# S5D3_MCU_only_edge_Power_SPI.net
KiCad netlist of a schematic drawn in EAGLE
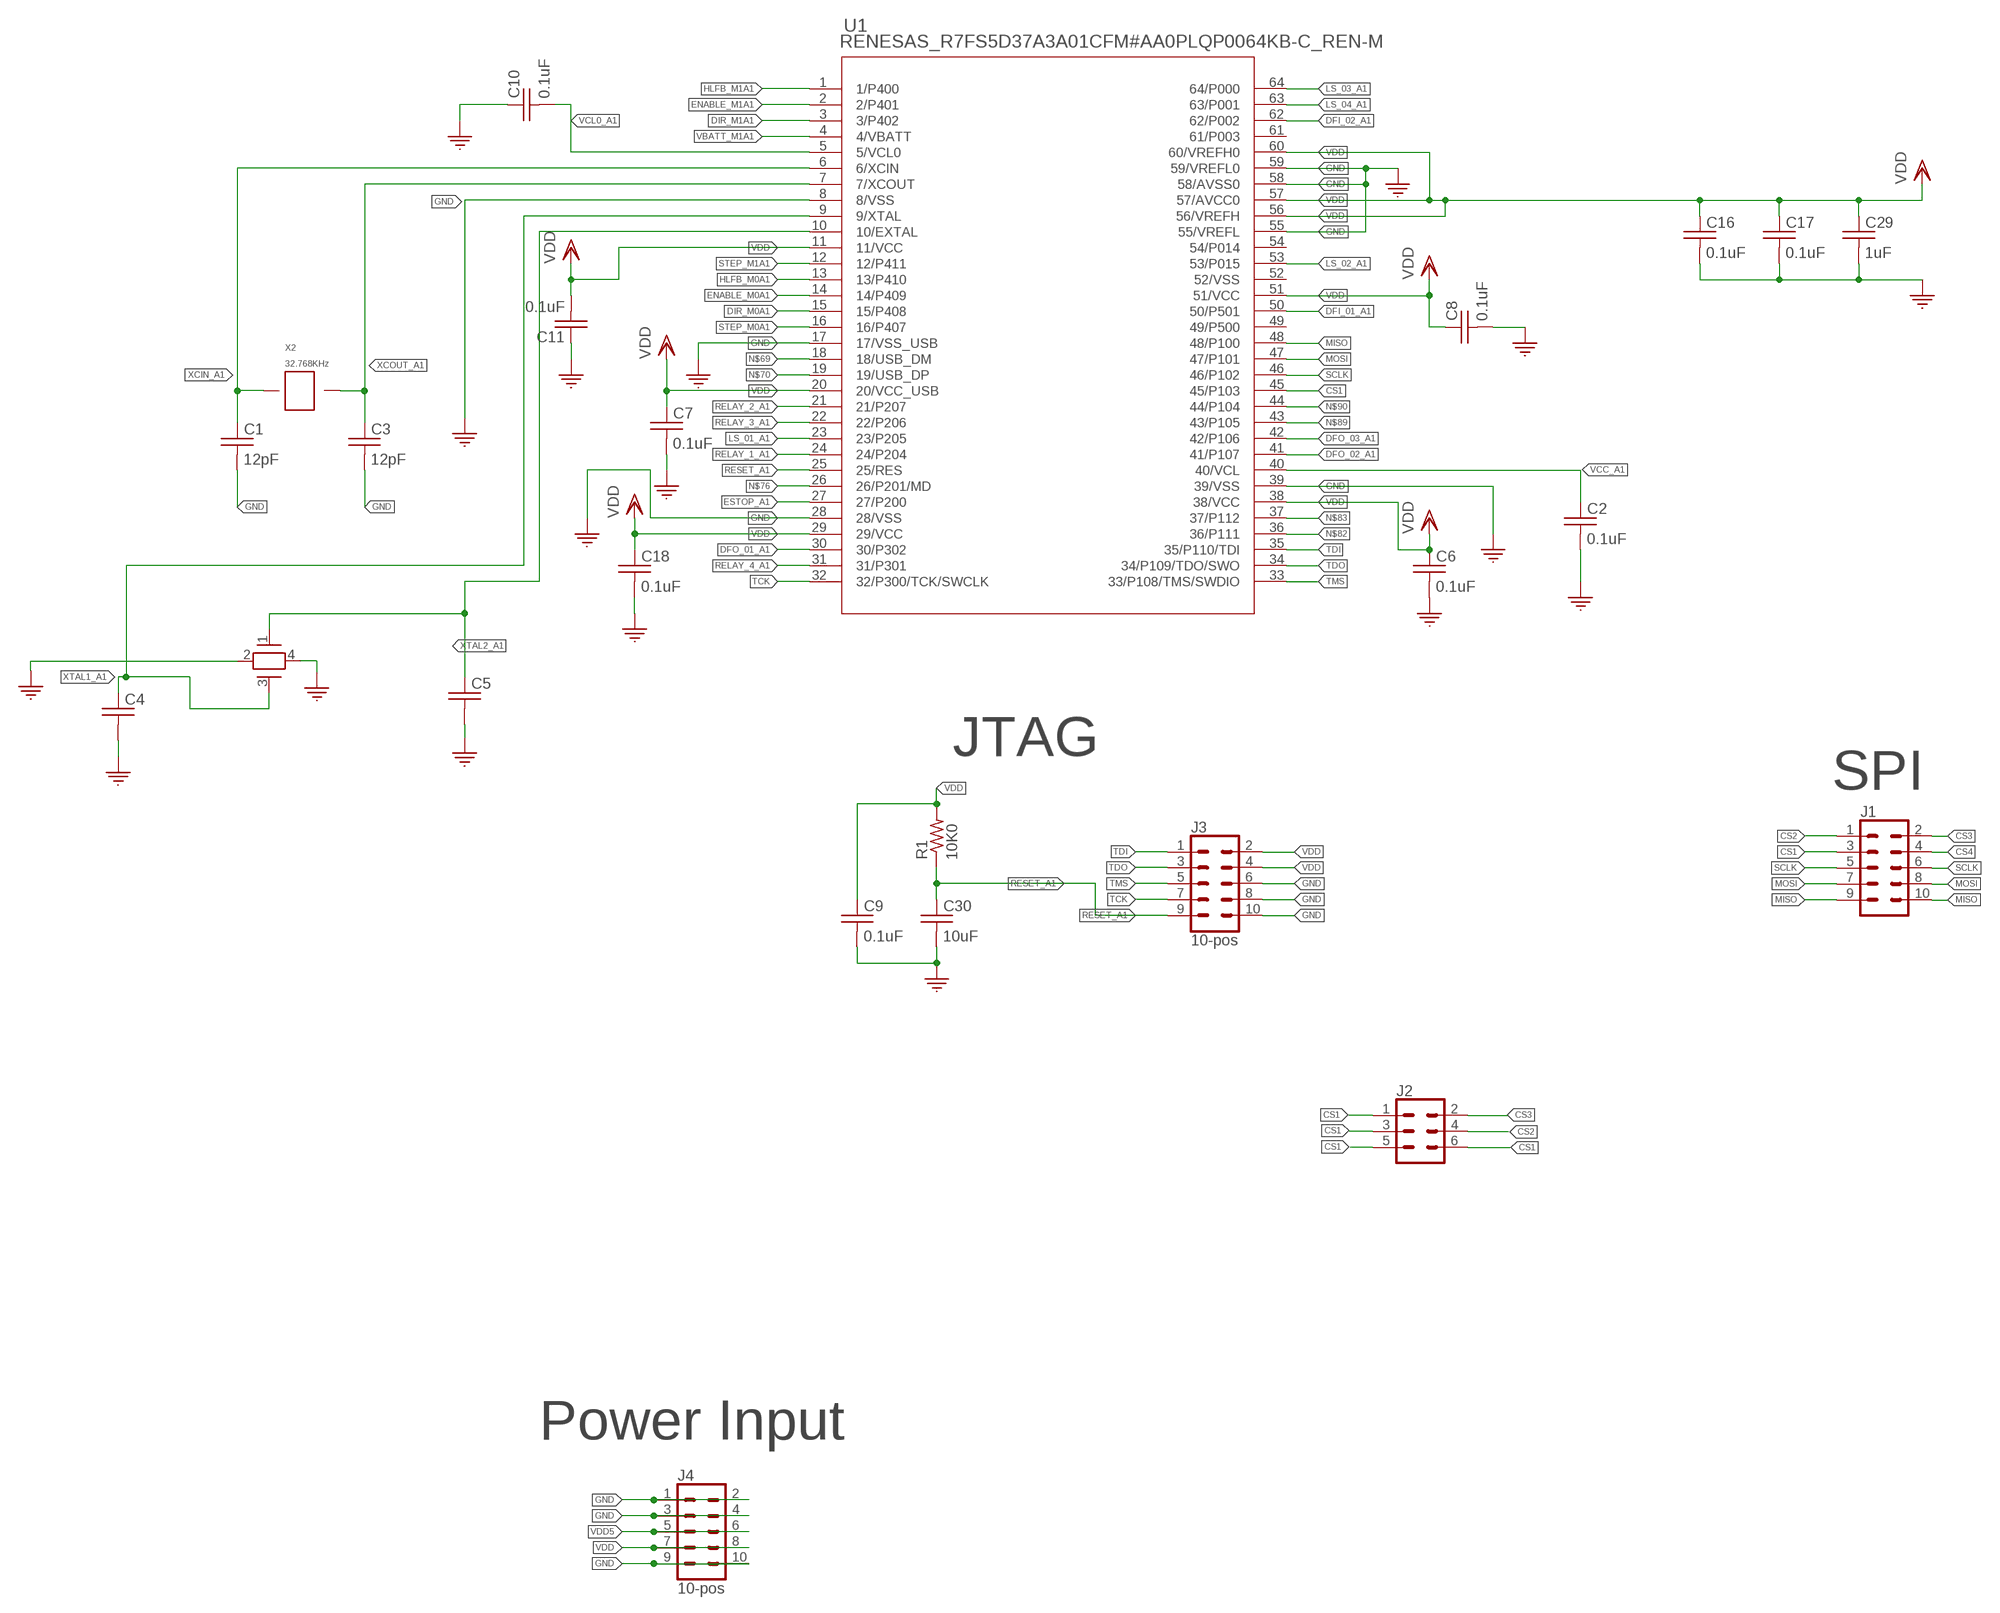
[diagram p0: schematic, sheet 1]

(export (version "E")
  (design (tool "Eeschema 10.0.6"))
  (components
    (comp (ref "C1")
      (value "12pF")
      (footprint "eagle-import:0402")
      (fields (field (name "PARTNO") "CL05C120JB5NNNC"))
      (libsource (lib "eagle-import") (part "C_0402_12PF"))
    )
    (comp (ref "C2")
      (value "0.1uF")
      (footprint "eagle-import:0402")
      (fields (field (name "PARTNO") "CL05F104ZO5NNNC"))
      (libsource (lib "eagle-import") (part "C_0402_0.1UF"))
    )
    (comp (ref "C3")
      (value "12pF")
      (footprint "eagle-import:0402")
      (fields (field (name "PARTNO") "CL05C120JB5NNNC"))
      (libsource (lib "eagle-import") (part "C_0402_12PF"))
    )
    (comp (ref "C4")
      (value "10pF")
      (footprint "eagle-import:0402")
      (fields (field (name "PARTNO") "CC0402JRNPO9BN100"))
      (libsource (lib "eagle-import") (part "C_0402_10PF"))
    )
    (comp (ref "C5")
      (value "10pF")
      (footprint "eagle-import:0402")
      (fields (field (name "PARTNO") "CC0402JRNPO9BN100"))
      (libsource (lib "eagle-import") (part "C_0402_10PF"))
    )
    (comp (ref "C6")
      (value "0.1uF")
      (footprint "eagle-import:0402")
      (fields (field (name "PARTNO") "CL05F104ZO5NNNC"))
      (libsource (lib "eagle-import") (part "C_0402_0.1UF"))
    )
    (comp (ref "C7")
      (value "0.1uF")
      (footprint "eagle-import:0402")
      (fields (field (name "PARTNO") "CL05F104ZO5NNNC"))
      (libsource (lib "eagle-import") (part "C_0402_0.1UF"))
    )
    (comp (ref "C8")
      (value "0.1uF")
      (footprint "eagle-import:0402")
      (fields (field (name "PARTNO") "CL05F104ZO5NNNC"))
      (libsource (lib "eagle-import") (part "C_0402_0.1UF"))
    )
    (comp (ref "C9")
      (value "0.1uF")
      (footprint "eagle-import:0402")
      (fields (field (name "PARTNO") "CL05F104ZO5NNNC"))
      (libsource (lib "eagle-import") (part "C_0402_0.1UF"))
    )
    (comp (ref "C10")
      (value "0.1uF")
      (footprint "eagle-import:0402")
      (fields (field (name "PARTNO") "CL05F104ZO5NNNC"))
      (libsource (lib "eagle-import") (part "C_0402_0.1UF"))
    )
    (comp (ref "C11")
      (value "0.1uF")
      (footprint "eagle-import:0402")
      (fields (field (name "PARTNO") "CL05F104ZO5NNNC"))
      (libsource (lib "eagle-import") (part "C_0402_0.1UF"))
    )
    (comp (ref "C16")
      (value "0.1uF")
      (footprint "eagle-import:0402")
      (fields (field (name "PARTNO") "CL05F104ZO5NNNC"))
      (libsource (lib "eagle-import") (part "C_0402_0.1UF"))
    )
    (comp (ref "C17")
      (value "0.1uF")
      (footprint "eagle-import:0402")
      (fields (field (name "PARTNO") "CL05F104ZO5NNNC"))
      (libsource (lib "eagle-import") (part "C_0402_0.1UF"))
    )
    (comp (ref "C18")
      (value "0.1uF")
      (footprint "eagle-import:0402")
      (fields (field (name "PARTNO") "CL05F104ZO5NNNC"))
      (libsource (lib "eagle-import") (part "C_0402_0.1UF"))
    )
    (comp (ref "C29")
      (value "1uF")
      (footprint "eagle-import:0402")
      (fields (field (name "PARTNO") "CL05A105KO5NNNC"))
      (libsource (lib "eagle-import") (part "C_0402_1UF"))
    )
    (comp (ref "C30")
      (value "10uF")
      (footprint "eagle-import:0402")
      (fields (field (name "PARTNO") "CL05A106MP8NUB8"))
      (libsource (lib "eagle-import") (part "C_0402_10UF"))
    )
    (comp (ref "J1")
      (value "CONN_05X2PTH")
      (footprint "eagle-import:2X5")
      (libsource (lib "eagle-import") (part "CONN_05X2PTH"))
    )
    (comp (ref "J2")
      (value "CONN_03X2")
      (footprint "eagle-import:2X3")
      (libsource (lib "eagle-import") (part "CONN_03X2"))
    )
    (comp (ref "J3")
      (value "10-pos")
      (footprint "eagle-import:2X5")
      (fields (field (name "PARTNO") "PH2RA-10-UA"))
      (libsource (lib "eagle-import") (part "CONN_05X2_RAPTH"))
    )
    (comp (ref "J4")
      (value "10-pos")
      (footprint "eagle-import:2X5")
      (fields (field (name "PARTNO") "PH2RA-10-UA"))
      (libsource (lib "eagle-import") (part "CONN_05X2_RAPTH"))
    )
    (comp (ref "R1")
      (value "10K0")
      (footprint "eagle-import:0402")
      (fields (field (name "PARTNO") "RMCF0402JT10K0"))
      (libsource (lib "eagle-import") (part "R_0402_10K0"))
    )
    (comp (ref "U1")
      (value "RENESAS_R7FS5D37A3A01CFM#AA0PLQP0064KB-C_REN-M")
      (footprint "eagle-import:PLQP0064KB-C_REN-M")
      (fields
        (field (name "PARTNO") "R7FS3A37A3A01CFM#AA0")
        (field (name "COPYRIGHT") "Copyright (C) 2023 Ultra Librarian. All rights reserved.")
      )
      (libsource (lib "eagle-import") (part "RENESAS_R7FS5D37A3A01CFM#AA0PLQP0064KB-C_REN-M"))
    )
    (comp (ref "X2")
      (value "32.768KHz")
      (footprint "eagle-import:SMD_X_2_PADS")
      (fields (field (name "PARTNO") "ABS07-32.768KHZ-T"))
      (libsource (lib "eagle-import") (part "XTAL_32.768KHZ"))
    )
    (comp (ref "Y1")
      (value "XTAL_12MHZ_ABM8G-12.000MHZ-B4Y-T")
      (footprint "eagle-import:CRYSTAL_ABM8G_ABR")
      (fields
        (field (name "PARTNO") "ABM8G-12.000MHZ-B4Y-T")
        (field (name "COPYRIGHT") "Copyright (C) 2023 Ultra Librarian. All rights reserved.")
      )
      (libsource (lib "eagle-import") (part "XTAL_12MHZ_ABM8G-12.000MHZ-B4Y-T"))
    )
  )
  (nets
    (net (code "1") (name "CS1") (class "Default")
      (node (ref "J1") (pin "3") (pinfunction "3_3") (pintype "passive"))
      (node (ref "J2") (pin "1") (pinfunction "1_1") (pintype "passive"))
      (node (ref "J2") (pin "3") (pinfunction "3_3") (pintype "passive"))
      (node (ref "J2") (pin "5") (pinfunction "5_5") (pintype "passive"))
      (node (ref "J2") (pin "6") (pinfunction "6_6") (pintype "passive"))
      (node (ref "U1") (pin "45") (pinfunction "45/P103_45") (pintype "bidirectional"))
    )
    (net (code "2") (name "CS2") (class "Default")
      (node (ref "J1") (pin "1") (pinfunction "1_1") (pintype "passive"))
      (node (ref "J2") (pin "4") (pinfunction "4_4") (pintype "passive"))
    )
    (net (code "3") (name "CS3") (class "Default")
      (node (ref "J1") (pin "2") (pinfunction "2_2") (pintype "passive"))
      (node (ref "J2") (pin "2") (pinfunction "2_2") (pintype "passive"))
    )
    (net (code "4") (name "CS4") (class "Default")
      (node (ref "J1") (pin "4") (pinfunction "4_4") (pintype "passive"))
    )
    (net (code "5") (name "DFI_01_A1") (class "Default")
      (node (ref "U1") (pin "50") (pinfunction "50/P501_50") (pintype "bidirectional"))
    )
    (net (code "6") (name "DFI_02_A1") (class "Default")
      (node (ref "U1") (pin "62") (pinfunction "62/P002_62") (pintype "bidirectional"))
    )
    (net (code "7") (name "DFO_01_A1") (class "Default")
      (node (ref "U1") (pin "30") (pinfunction "30/P302_30") (pintype "bidirectional"))
    )
    (net (code "8") (name "DFO_02_A1") (class "Default")
      (node (ref "U1") (pin "41") (pinfunction "41/P107_41") (pintype "bidirectional"))
    )
    (net (code "9") (name "DFO_03_A1") (class "Default")
      (node (ref "U1") (pin "42") (pinfunction "42/P106_42") (pintype "bidirectional"))
    )
    (net (code "10") (name "DIR_M0A1") (class "Default")
      (node (ref "U1") (pin "15") (pinfunction "15/P408_15") (pintype "bidirectional"))
    )
    (net (code "11") (name "DIR_M1A1") (class "Default")
      (node (ref "U1") (pin "3") (pinfunction "3/P402_3") (pintype "bidirectional"))
    )
    (net (code "12") (name "ENABLE_M0A1") (class "Default")
      (node (ref "U1") (pin "14") (pinfunction "14/P409_14") (pintype "bidirectional"))
    )
    (net (code "13") (name "ENABLE_M1A1") (class "Default")
      (node (ref "U1") (pin "2") (pinfunction "2/P401_2") (pintype "bidirectional"))
    )
    (net (code "14") (name "ESTOP_A1") (class "Default")
      (node (ref "U1") (pin "27") (pinfunction "27/P200_27") (pintype "bidirectional"))
    )
    (net (code "15") (name "GND") (class "Default")
      (node (ref "C1") (pin "P$2") (pinfunction "2_P$2") (pintype "passive"))
      (node (ref "C10") (pin "P$1") (pinfunction "1_P$1") (pintype "passive"))
      (node (ref "C11") (pin "P$1") (pinfunction "1_P$1") (pintype "passive"))
      (node (ref "C16") (pin "P$2") (pinfunction "2_P$2") (pintype "passive"))
      (node (ref "C17") (pin "P$2") (pinfunction "2_P$2") (pintype "passive"))
      (node (ref "C18") (pin "P$2") (pinfunction "2_P$2") (pintype "passive"))
      (node (ref "C2") (pin "P$2") (pinfunction "2_P$2") (pintype "passive"))
      (node (ref "C29") (pin "P$2") (pinfunction "2_P$2") (pintype "passive"))
      (node (ref "C3") (pin "P$2") (pinfunction "2_P$2") (pintype "passive"))
      (node (ref "C30") (pin "P$2") (pinfunction "2_P$2") (pintype "passive"))
      (node (ref "C4") (pin "P$2") (pinfunction "2_P$2") (pintype "passive"))
      (node (ref "C5") (pin "P$2") (pinfunction "2_P$2") (pintype "passive"))
      (node (ref "C6") (pin "P$2") (pinfunction "2_P$2") (pintype "passive"))
      (node (ref "C7") (pin "P$2") (pinfunction "2_P$2") (pintype "passive"))
      (node (ref "C8") (pin "P$2") (pinfunction "2_P$2") (pintype "passive"))
      (node (ref "C9") (pin "P$2") (pinfunction "2_P$2") (pintype "passive"))
      (node (ref "J3") (pin "10") (pinfunction "10_10") (pintype "passive"))
      (node (ref "J3") (pin "6") (pinfunction "6_6") (pintype "passive"))
      (node (ref "J3") (pin "8") (pinfunction "8_8") (pintype "passive"))
      (node (ref "J4") (pin "1") (pinfunction "1_1") (pintype "passive"))
      (node (ref "J4") (pin "10") (pinfunction "10_10") (pintype "passive"))
      (node (ref "J4") (pin "2") (pinfunction "2_2") (pintype "passive"))
      (node (ref "J4") (pin "3") (pinfunction "3_3") (pintype "passive"))
      (node (ref "J4") (pin "4") (pinfunction "4_4") (pintype "passive"))
      (node (ref "J4") (pin "9") (pinfunction "9_9") (pintype "passive"))
      (node (ref "U1") (pin "17") (pinfunction "17/VSS_USB_17") (pintype "power_in"))
      (node (ref "U1") (pin "28") (pinfunction "28/VSS_28") (pintype "bidirectional"))
      (node (ref "U1") (pin "39") (pinfunction "39/VSS_39") (pintype "power_in"))
      (node (ref "U1") (pin "55") (pinfunction "55/VREFL_55") (pintype "bidirectional"))
      (node (ref "U1") (pin "58") (pinfunction "58/AVSS0_58") (pintype "bidirectional"))
      (node (ref "U1") (pin "59") (pinfunction "59/VREFL0_59") (pintype "bidirectional"))
      (node (ref "U1") (pin "8") (pinfunction "8/VSS_8") (pintype "power_in"))
      (node (ref "Y1") (pin "2") (pinfunction "2_2") (pintype "passive"))
      (node (ref "Y1") (pin "4") (pinfunction "4_4") (pintype "passive"))
    )
    (net (code "16") (name "HLFB_M0A1") (class "Default")
      (node (ref "U1") (pin "13") (pinfunction "13/P410_13") (pintype "bidirectional"))
    )
    (net (code "17") (name "HLFB_M1A1") (class "Default")
      (node (ref "U1") (pin "1") (pinfunction "1/P400_1") (pintype "bidirectional"))
    )
    (net (code "18") (name "LS_01_A1") (class "Default")
      (node (ref "U1") (pin "23") (pinfunction "23/P205_23") (pintype "bidirectional"))
    )
    (net (code "19") (name "LS_02_A1") (class "Default")
      (node (ref "U1") (pin "53") (pinfunction "53/P015_53") (pintype "bidirectional"))
    )
    (net (code "20") (name "LS_03_A1") (class "Default")
      (node (ref "U1") (pin "64") (pinfunction "64/P000_64") (pintype "bidirectional"))
    )
    (net (code "21") (name "LS_04_A1") (class "Default")
      (node (ref "U1") (pin "63") (pinfunction "63/P001_63") (pintype "bidirectional"))
    )
    (net (code "22") (name "MISO") (class "Default")
      (node (ref "J1") (pin "10") (pinfunction "10_10") (pintype "passive"))
      (node (ref "J1") (pin "9") (pinfunction "9_9") (pintype "passive"))
      (node (ref "U1") (pin "48") (pinfunction "48/P100_48") (pintype "bidirectional"))
    )
    (net (code "23") (name "MOSI") (class "Default")
      (node (ref "J1") (pin "7") (pinfunction "7_7") (pintype "passive"))
      (node (ref "J1") (pin "8") (pinfunction "8_8") (pintype "passive"))
      (node (ref "U1") (pin "47") (pinfunction "47/P101_47") (pintype "bidirectional"))
    )
    (net (code "24") (name "N$69") (class "Default")
      (node (ref "U1") (pin "18") (pinfunction "18/USB_DM_18") (pintype "bidirectional"))
    )
    (net (code "25") (name "N$70") (class "Default")
      (node (ref "U1") (pin "19") (pinfunction "19/USB_DP_19") (pintype "bidirectional"))
    )
    (net (code "26") (name "N$76") (class "Default")
      (node (ref "U1") (pin "26") (pinfunction "26/P201/MD_26") (pintype "bidirectional"))
    )
    (net (code "27") (name "N$82") (class "Default")
      (node (ref "U1") (pin "36") (pinfunction "36/P111_36") (pintype "bidirectional"))
    )
    (net (code "28") (name "N$83") (class "Default")
      (node (ref "U1") (pin "37") (pinfunction "37/P112_37") (pintype "bidirectional"))
    )
    (net (code "29") (name "N$89") (class "Default")
      (node (ref "U1") (pin "43") (pinfunction "43/P105_43") (pintype "bidirectional"))
    )
    (net (code "30") (name "N$90") (class "Default")
      (node (ref "U1") (pin "44") (pinfunction "44/P104_44") (pintype "bidirectional"))
    )
    (net (code "31") (name "RELAY_1_A1") (class "Default")
      (node (ref "U1") (pin "24") (pinfunction "24/P204_24") (pintype "bidirectional"))
    )
    (net (code "32") (name "RELAY_2_A1") (class "Default")
      (node (ref "U1") (pin "21") (pinfunction "21/P207_21") (pintype "power_in"))
    )
    (net (code "33") (name "RELAY_3_A1") (class "Default")
      (node (ref "U1") (pin "22") (pinfunction "22/P206_22") (pintype "bidirectional"))
    )
    (net (code "34") (name "RELAY_4_A1") (class "Default")
      (node (ref "U1") (pin "31") (pinfunction "31/P301_31") (pintype "bidirectional"))
    )
    (net (code "35") (name "RESET_A1") (class "Default")
      (node (ref "C30") (pin "P$1") (pinfunction "1_P$1") (pintype "passive"))
      (node (ref "J3") (pin "9") (pinfunction "9_9") (pintype "passive"))
      (node (ref "R1") (pin "P$1") (pinfunction "1_P$1") (pintype "passive"))
      (node (ref "U1") (pin "25") (pinfunction "25/RES_25") (pintype "input"))
    )
    (net (code "36") (name "SCLK") (class "Default")
      (node (ref "J1") (pin "5") (pinfunction "5_5") (pintype "passive"))
      (node (ref "J1") (pin "6") (pinfunction "6_6") (pintype "passive"))
      (node (ref "U1") (pin "46") (pinfunction "46/P102_46") (pintype "bidirectional"))
    )
    (net (code "37") (name "STEP_M0A1") (class "Default")
      (node (ref "U1") (pin "16") (pinfunction "16/P407_16") (pintype "bidirectional"))
    )
    (net (code "38") (name "STEP_M1A1") (class "Default")
      (node (ref "U1") (pin "12") (pinfunction "12/P411_12") (pintype "bidirectional"))
    )
    (net (code "39") (name "TCK") (class "Default")
      (node (ref "J3") (pin "7") (pinfunction "7_7") (pintype "passive"))
      (node (ref "U1") (pin "32") (pinfunction "32/P300/TCK/SWCLK_32") (pintype "bidirectional"))
    )
    (net (code "40") (name "TDI") (class "Default")
      (node (ref "J3") (pin "1") (pinfunction "1_1") (pintype "passive"))
      (node (ref "U1") (pin "35") (pinfunction "35/P110/TDI_35") (pintype "bidirectional"))
    )
    (net (code "41") (name "TDO") (class "Default")
      (node (ref "J3") (pin "3") (pinfunction "3_3") (pintype "passive"))
      (node (ref "U1") (pin "34") (pinfunction "34/P109/TDO/SWO_34") (pintype "bidirectional"))
    )
    (net (code "42") (name "TMS") (class "Default")
      (node (ref "J3") (pin "5") (pinfunction "5_5") (pintype "passive"))
      (node (ref "U1") (pin "33") (pinfunction "33/P108/TMS/SWDIO_33") (pintype "bidirectional"))
    )
    (net (code "43") (name "VBATT_M1A1") (class "Default")
      (node (ref "U1") (pin "4") (pinfunction "4/VBATT_4") (pintype "power_in"))
    )
    (net (code "44") (name "VCC_A1") (class "Default")
      (node (ref "C2") (pin "P$1") (pinfunction "1_P$1") (pintype "passive"))
      (node (ref "U1") (pin "40") (pinfunction "40/VCL_40") (pintype "power_in"))
    )
    (net (code "45") (name "VCL0_A1") (class "Default")
      (node (ref "C10") (pin "P$2") (pinfunction "2_P$2") (pintype "passive"))
      (node (ref "U1") (pin "5") (pinfunction "5/VCL0_5") (pintype "power_in"))
    )
    (net (code "46") (name "VDD") (class "Default")
      (node (ref "C11") (pin "P$2") (pinfunction "2_P$2") (pintype "passive"))
      (node (ref "C16") (pin "P$1") (pinfunction "1_P$1") (pintype "passive"))
      (node (ref "C17") (pin "P$1") (pinfunction "1_P$1") (pintype "passive"))
      (node (ref "C18") (pin "P$1") (pinfunction "1_P$1") (pintype "passive"))
      (node (ref "C29") (pin "P$1") (pinfunction "1_P$1") (pintype "passive"))
      (node (ref "C6") (pin "P$1") (pinfunction "1_P$1") (pintype "passive"))
      (node (ref "C7") (pin "P$1") (pinfunction "1_P$1") (pintype "passive"))
      (node (ref "C8") (pin "P$1") (pinfunction "1_P$1") (pintype "passive"))
      (node (ref "C9") (pin "P$1") (pinfunction "1_P$1") (pintype "passive"))
      (node (ref "J3") (pin "2") (pinfunction "2_2") (pintype "passive"))
      (node (ref "J3") (pin "4") (pinfunction "4_4") (pintype "passive"))
      (node (ref "J4") (pin "7") (pinfunction "7_7") (pintype "passive"))
      (node (ref "J4") (pin "8") (pinfunction "8_8") (pintype "passive"))
      (node (ref "R1") (pin "P$2") (pinfunction "2_P$2") (pintype "passive"))
      (node (ref "U1") (pin "11") (pinfunction "11/VCC_11") (pintype "power_in"))
      (node (ref "U1") (pin "20") (pinfunction "20/VCC_USB_20") (pintype "power_in"))
      (node (ref "U1") (pin "29") (pinfunction "29/VCC_29") (pintype "bidirectional"))
      (node (ref "U1") (pin "38") (pinfunction "38/VCC_38") (pintype "bidirectional"))
      (node (ref "U1") (pin "51") (pinfunction "51/VCC_51") (pintype "bidirectional"))
      (node (ref "U1") (pin "56") (pinfunction "56/VREFH_56") (pintype "power_in"))
      (node (ref "U1") (pin "57") (pinfunction "57/AVCC0_57") (pintype "power_in"))
      (node (ref "U1") (pin "60") (pinfunction "60/VREFH0_60") (pintype "bidirectional"))
    )
    (net (code "47") (name "VDD5") (class "Default")
      (node (ref "J4") (pin "5") (pinfunction "5_5") (pintype "passive"))
      (node (ref "J4") (pin "6") (pinfunction "6_6") (pintype "passive"))
    )
    (net (code "48") (name "XCIN_A1") (class "Default")
      (node (ref "C1") (pin "P$1") (pinfunction "1_P$1") (pintype "passive"))
      (node (ref "U1") (pin "6") (pinfunction "6/XCIN_6") (pintype "bidirectional"))
      (node (ref "X2") (pin "P$1") (pinfunction "P$1_P$1") (pintype "bidirectional"))
    )
    (net (code "49") (name "XCOUT_A1") (class "Default")
      (node (ref "C3") (pin "P$1") (pinfunction "1_P$1") (pintype "passive"))
      (node (ref "U1") (pin "7") (pinfunction "7/XCOUT_7") (pintype "bidirectional"))
      (node (ref "X2") (pin "P$2") (pinfunction "P$2_P$2") (pintype "bidirectional"))
    )
    (net (code "50") (name "XTAL1_A1") (class "Default")
      (node (ref "C4") (pin "P$1") (pinfunction "1_P$1") (pintype "passive"))
      (node (ref "U1") (pin "9") (pinfunction "9/XTAL_9") (pintype "bidirectional"))
      (node (ref "Y1") (pin "3") (pinfunction "3_3") (pintype "passive"))
    )
    (net (code "51") (name "XTAL2_A1") (class "Default")
      (node (ref "C5") (pin "P$1") (pinfunction "1_P$1") (pintype "passive"))
      (node (ref "U1") (pin "10") (pinfunction "10/EXTAL_10") (pintype "bidirectional"))
      (node (ref "Y1") (pin "1") (pinfunction "1_1") (pintype "passive"))
    )
    (net (code "52") (name "unconnected-(U1-49{slash}P500-Pad49)") (class "Default")
      (node (ref "U1") (pin "49") (pinfunction "49/P500_49") (pintype "bidirectional"))
    )
    (net (code "53") (name "unconnected-(U1-52{slash}VSS-Pad52)") (class "Default")
      (node (ref "U1") (pin "52") (pinfunction "52/VSS_52") (pintype "bidirectional"))
    )
    (net (code "54") (name "unconnected-(U1-54{slash}P014-Pad54)") (class "Default")
      (node (ref "U1") (pin "54") (pinfunction "54/P014_54") (pintype "bidirectional"))
    )
    (net (code "55") (name "unconnected-(U1-61{slash}P003-Pad61)") (class "Default")
      (node (ref "U1") (pin "61") (pinfunction "61/P003_61") (pintype "bidirectional"))
    )
  )
)
